# Balance_V0_1.net
KiCad netlist of a schematic drawn in Altium Designer
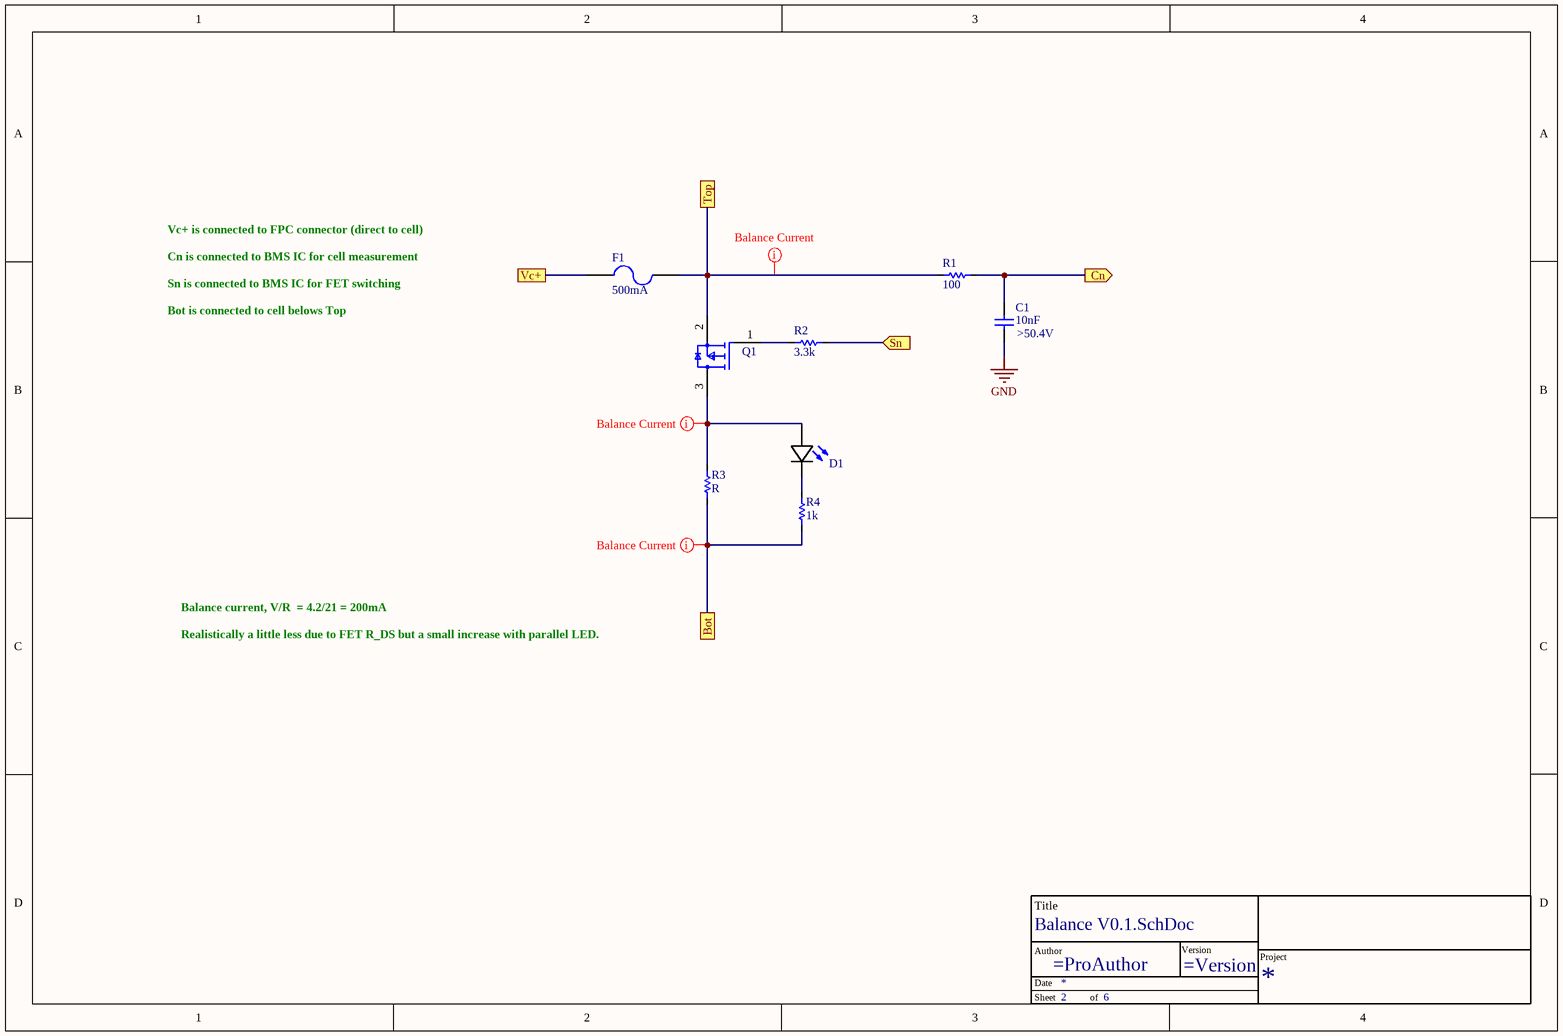
[diagram p0: Balance V0.1.SchDoc]

(export (version "E")
  (design (tool "Eeschema 10.0.6"))
  (components
    (comp (ref "*") (value "TitleBlock") (libsource (lib "SchematicLib") (part "TitleBlock")))
    (comp (ref "C1")
      (value "10nF")
      (footprint "C_0603")
      (description "Capacitor")
      (fields (field (name "VOLTAGE") ">50.4V") (field (name "Comment") "C"))
      (libsource (lib "Passives") (part "Capacitor"))
    )
    (comp (ref "D1")
      (value "150060BS55040")
      (footprint "LED (0603)")
      (description "LED BLUE DIFFUSED 0603 SMD")
      (fields (field (name "MANUFACTURER") "Wurth Electronics"))
      (libsource (lib "LEDLib") (part "150060BS55040"))
    )
    (comp (ref "F1")
      (value "0466.500NR")
      (footprint "0466.500NR")
      (fields
        (field (name "MANUFACTURER") "Littelfuse")
        (field (name "CURRENT RATING") "500mA")
        (field (name "PUBLISHER") "Altium Limited")
      )
      (libsource (lib "Miscellaneous Devices") (part "Fuse 2"))
    )
    (comp (ref "Q1")
      (value "NX2301P,215")
      (footprint "FP-SOT23-MFG")
      (description "MOSFET P-CH 20V 2A TO-236AB")
      (libsource (lib "Altium Content Vault") (part "882370683d780ecf8f33bea6fe01d97"))
    )
    (comp (ref "R1")
      (value "100")
      (footprint "R-0603")
      (description "Resistor")
      (libsource (lib "Passives") (part "Resistor"))
    )
    (comp (ref "R2")
      (value "3.3k")
      (footprint "R-0603")
      (description "Resistor")
      (libsource (lib "Passives") (part "Resistor"))
    )
    (comp (ref "R3")
      (value "R")
      (footprint "R_2512")
      (description "Resistor")
      (libsource (lib "Passives") (part "Resistor"))
    )
    (comp (ref "R4")
      (value "1k")
      (footprint "R-0603")
      (description "Resistor")
      (libsource (lib "Passives") (part "Resistor"))
    )
  )
  (nets
    (net (code "1") (name "/Bot") (class "Default")
      (node (ref "R3") (pin "1") (pinfunction "1_1") (pintype "passive"))
      (node (ref "R4") (pin "1") (pinfunction "1_1") (pintype "passive"))
    )
    (net (code "2") (name "/Cn") (class "Default")
      (node (ref "C1") (pin "2") (pinfunction "2_2") (pintype "passive"))
      (node (ref "R1") (pin "2") (pinfunction "2_2") (pintype "passive"))
    )
    (net (code "3") (name "/Sn") (class "Default")
      (node (ref "R2") (pin "2") (pinfunction "2_2") (pintype "passive"))
    )
    (net (code "4") (name "/Top") (class "Default")
      (node (ref "F1") (pin "2") (pinfunction "2_2") (pintype "passive"))
      (node (ref "Q1") (pin "2") (pinfunction "S_2") (pintype "passive"))
      (node (ref "R1") (pin "1") (pinfunction "1_1") (pintype "passive"))
    )
    (net (code "5") (name "/Vc+") (class "Default")
      (node (ref "F1") (pin "1") (pinfunction "1_1") (pintype "passive"))
    )
    (net (code "6") (name "GND") (class "Default")
      (node (ref "C1") (pin "1") (pinfunction "1_1") (pintype "passive"))
    )
    (net (code "7") (name "Net-(D1-A)") (class "Default")
      (node (ref "D1") (pin "2") (pinfunction "A_2") (pintype "passive"))
      (node (ref "Q1") (pin "3") (pinfunction "D_3") (pintype "passive"))
      (node (ref "R3") (pin "2") (pinfunction "2_2") (pintype "passive"))
    )
    (net (code "8") (name "Net-(D1-K)") (class "Default")
      (node (ref "D1") (pin "1") (pinfunction "K_1") (pintype "passive"))
      (node (ref "R4") (pin "2") (pinfunction "2_2") (pintype "passive"))
    )
    (net (code "9") (name "Net-(Q1-G)") (class "Default")
      (node (ref "Q1") (pin "1") (pinfunction "G_1") (pintype "passive"))
      (node (ref "R2") (pin "1") (pinfunction "1_1") (pintype "passive"))
    )
  )
)
